# esp8266-dev.net
KiCad netlist of a schematic drawn in EAGLE
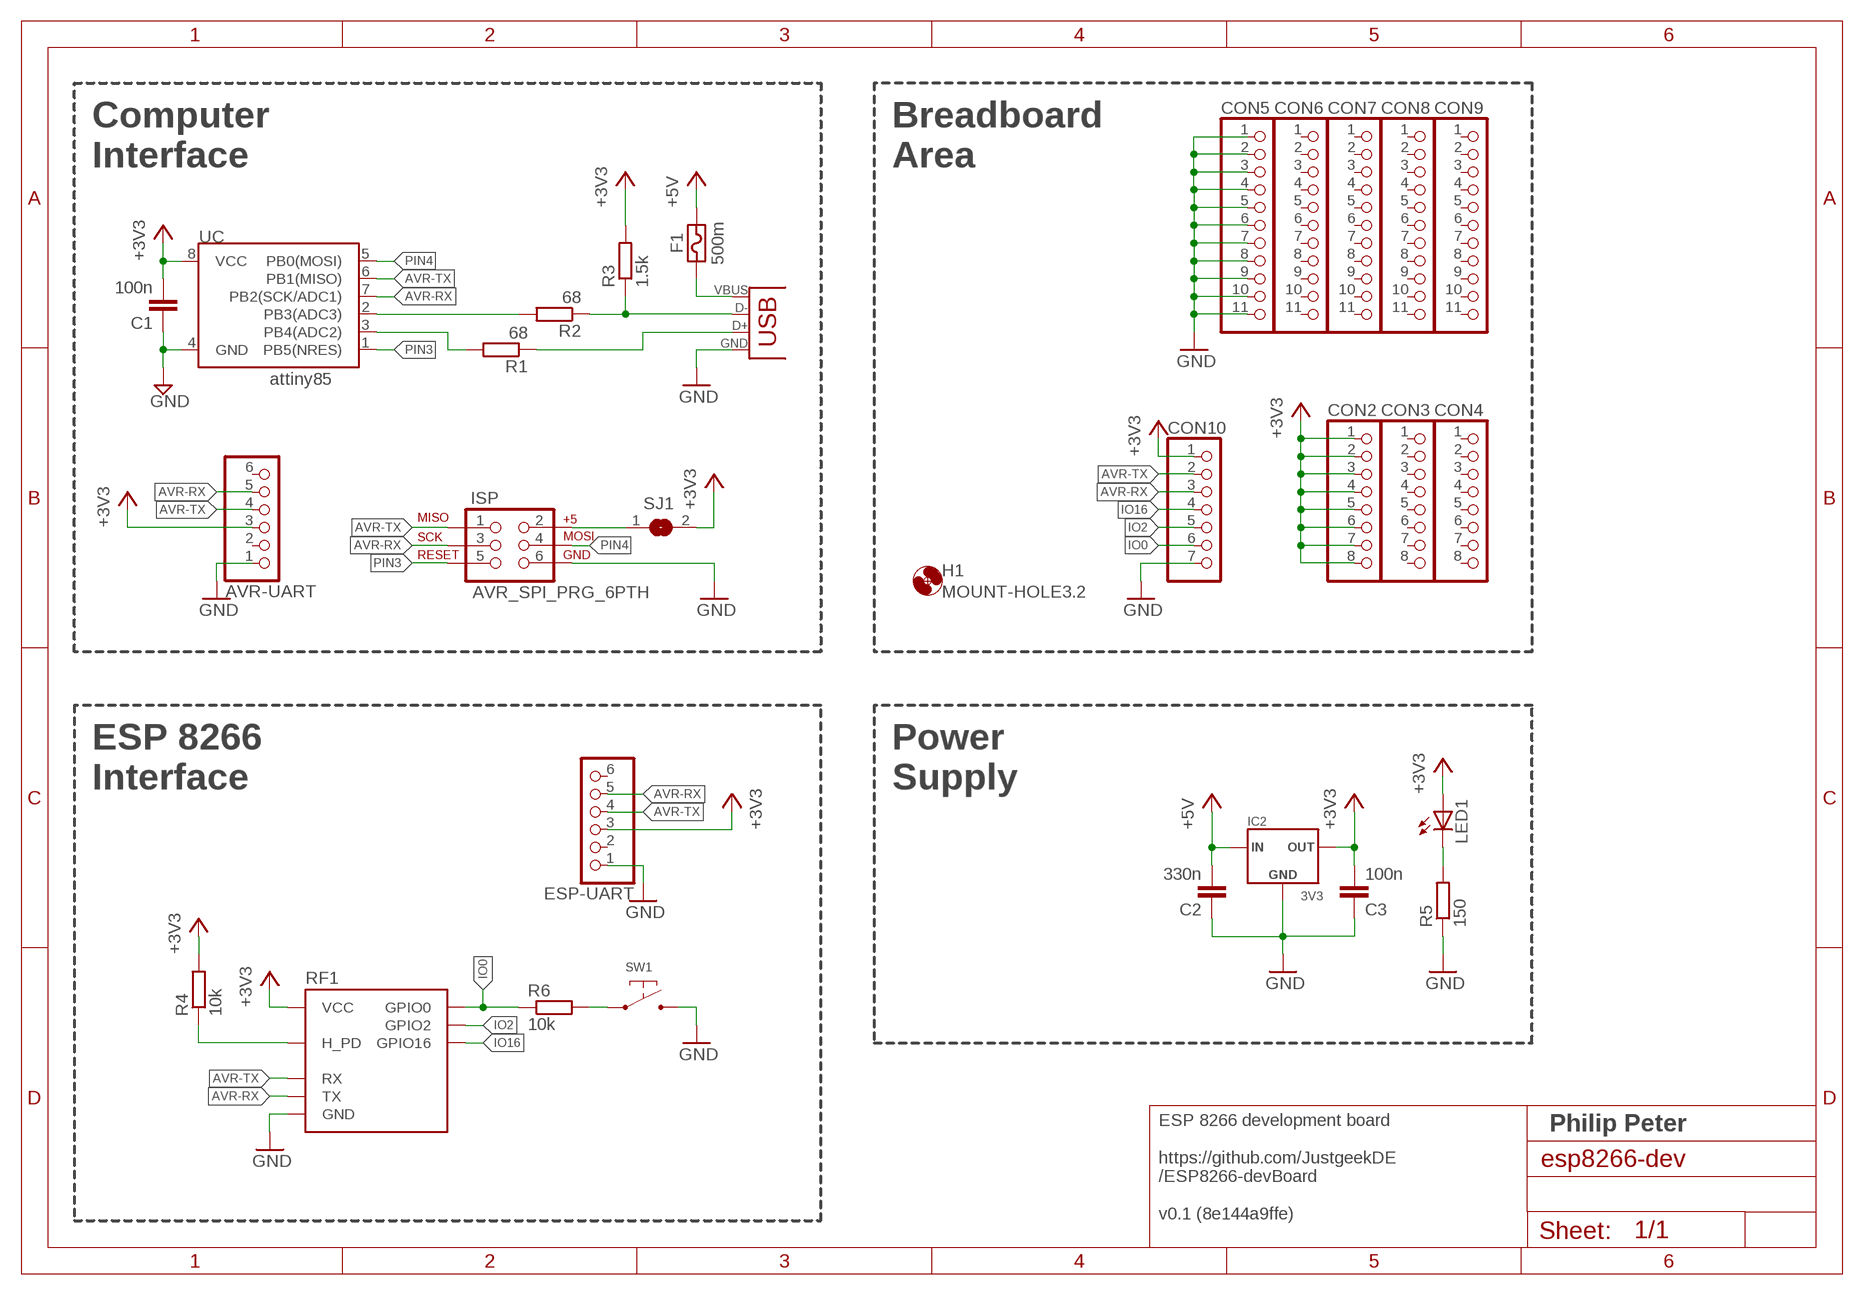
[diagram p0: schematic, sheet 1]

(export (version "E")
  (design (tool "Eeschema 10.0.6"))
  (components
    (comp (ref "AVR-UART")
      (value "GENERIC-1X6STANDARD")
      (footprint "eagle-import:PINHEADER-100MIL-1X6")
      (libsource (lib "eagle-import") (part "GENERIC-1X6STANDARD"))
    )
    (comp (ref "C1")
      (value "100n")
      (footprint "eagle-import:C025-025X050")
      (libsource (lib "eagle-import") (part "C-EU025-025X050"))
    )
    (comp (ref "C2")
      (value "330n")
      (footprint "eagle-import:C025-025X050")
      (libsource (lib "eagle-import") (part "C-EU025-025X050"))
    )
    (comp (ref "C3")
      (value "100n")
      (footprint "eagle-import:C025-025X050")
      (libsource (lib "eagle-import") (part "C-EU025-025X050"))
    )
    (comp (ref "CON1")
      (value "USBB-SOCKET")
      (footprint "eagle-import:PN61729-S")
      (libsource (lib "eagle-import") (part "USBB-SOCKET"))
    )
    (comp (ref "CON2")
      (value "GENERIC-1X8NOSILK")
      (footprint "eagle-import:PINHEADER-100MIL-1X8-NOSILK")
      (libsource (lib "eagle-import") (part "GENERIC-1X8NOSILK"))
    )
    (comp (ref "CON3")
      (value "GENERIC-1X8NOSILK")
      (footprint "eagle-import:PINHEADER-100MIL-1X8-NOSILK")
      (libsource (lib "eagle-import") (part "GENERIC-1X8NOSILK"))
    )
    (comp (ref "CON4")
      (value "GENERIC-1X8NOSILK")
      (footprint "eagle-import:PINHEADER-100MIL-1X8-NOSILK")
      (libsource (lib "eagle-import") (part "GENERIC-1X8NOSILK"))
    )
    (comp (ref "CON5")
      (value "GENERIC-1X11NOSILK")
      (footprint "eagle-import:PINHEADER-100MIL-1X11-NOSILK")
      (libsource (lib "eagle-import") (part "GENERIC-1X11NOSILK"))
    )
    (comp (ref "CON6")
      (value "GENERIC-1X11NOSILK")
      (footprint "eagle-import:PINHEADER-100MIL-1X11-NOSILK")
      (libsource (lib "eagle-import") (part "GENERIC-1X11NOSILK"))
    )
    (comp (ref "CON7")
      (value "GENERIC-1X11NOSILK")
      (footprint "eagle-import:PINHEADER-100MIL-1X11-NOSILK")
      (libsource (lib "eagle-import") (part "GENERIC-1X11NOSILK"))
    )
    (comp (ref "CON8")
      (value "GENERIC-1X11NOSILK")
      (footprint "eagle-import:PINHEADER-100MIL-1X11-NOSILK")
      (libsource (lib "eagle-import") (part "GENERIC-1X11NOSILK"))
    )
    (comp (ref "CON9")
      (value "GENERIC-1X11NOSILK")
      (footprint "eagle-import:PINHEADER-100MIL-1X11-NOSILK")
      (libsource (lib "eagle-import") (part "GENERIC-1X11NOSILK"))
    )
    (comp (ref "CON10")
      (value "GENERIC-1X7NOSILK")
      (footprint "eagle-import:PINHEADER-100MIL-1X7-NOSILK")
      (libsource (lib "eagle-import") (part "GENERIC-1X7NOSILK"))
    )
    (comp (ref "ESP-UART")
      (value "GENERIC-1X6STANDARD")
      (footprint "eagle-import:PINHEADER-100MIL-1X6")
      (libsource (lib "eagle-import") (part "GENERIC-1X6STANDARD"))
    )
    (comp (ref "F1")
      (value "500m")
      (footprint "eagle-import:FUSE-THT-100-MIL")
      (libsource (lib "eagle-import") (part "FUSETHT-5.1"))
    )
    (comp (ref "H1")
      (value "MOUNT-HOLE3.2")
      (footprint "eagle-import:3,2")
      (libsource (lib "eagle-import") (part "MOUNT-HOLE3.2"))
    )
    (comp (ref "IC2")
      (value "3V3")
      (footprint "eagle-import:TO220V")
      (libsource (lib "eagle-import") (part "REGULATOR-UA78M33TO220"))
    )
    (comp (ref "ISP")
      (value "AVR_SPI_PRG_6PTH")
      (footprint "eagle-import:2X3")
      (libsource (lib "eagle-import") (part "AVR_SPI_PRG_6PTH"))
    )
    (comp (ref "LED1")
      (value "LED3MM")
      (footprint "eagle-import:LED3MM")
      (libsource (lib "eagle-import") (part "LED3MM"))
    )
    (comp (ref "R1")
      (value "68")
      (footprint "eagle-import:0204_7")
      (libsource (lib "eagle-import") (part "R-EU_0204/7"))
    )
    (comp (ref "R2")
      (value "68")
      (footprint "eagle-import:0204_7")
      (libsource (lib "eagle-import") (part "R-EU_0204/7"))
    )
    (comp (ref "R3")
      (value "1.5k")
      (footprint "eagle-import:0204_7")
      (libsource (lib "eagle-import") (part "R-EU_0204/7"))
    )
    (comp (ref "R4")
      (value "10k")
      (footprint "eagle-import:0204_7")
      (libsource (lib "eagle-import") (part "R-EU_0204/7"))
    )
    (comp (ref "R5")
      (value "150")
      (footprint "eagle-import:0204_7")
      (libsource (lib "eagle-import") (part "R-EU_0204/7"))
    )
    (comp (ref "R6")
      (value "10k")
      (footprint "eagle-import:0204_7")
      (libsource (lib "eagle-import") (part "R-EU_0204/7"))
    )
    (comp (ref "RF1")
      (value "ESP2866-ESP-01THT-NOSILK")
      (footprint "eagle-import:ESP8266-ESP-01-NOSILK")
      (libsource (lib "eagle-import") (part "ESP2866-ESP-01THT-NOSILK"))
    )
    (comp (ref "SJ1") (value "SJ") (footprint "eagle-import:SJ") (libsource (lib "eagle-import") (part "SJ")))
    (comp (ref "SW1")
      (value "SWITCH-DEFAULT_OFF-DEFAULT")
      (footprint "eagle-import:SWITCH-GENERIC-4_PIN")
      (libsource (lib "eagle-import") (part "SWITCH-DEFAULT_OFF-DEFAULT"))
    )
    (comp (ref "UC")
      (value "ATTINY85")
      (footprint "eagle-import:DIP08")
      (libsource (lib "eagle-import") (part "ATTINY45DIP8"))
    )
  )
  (nets
    (net (code "1") (name "+3V3") (class "Default")
      (node (ref "AVR-UART") (pin "3") (pinfunction "3_3") (pintype "passive"))
      (node (ref "C1") (pin "2") (pinfunction "2_2") (pintype "passive"))
      (node (ref "C3") (pin "2") (pinfunction "2_2") (pintype "passive"))
      (node (ref "CON10") (pin "1") (pinfunction "1_1") (pintype "passive"))
      (node (ref "CON2") (pin "1") (pinfunction "1_1") (pintype "passive"))
      (node (ref "CON2") (pin "2") (pinfunction "2_2") (pintype "passive"))
      (node (ref "CON2") (pin "3") (pinfunction "3_3") (pintype "passive"))
      (node (ref "CON2") (pin "4") (pinfunction "4_4") (pintype "passive"))
      (node (ref "CON2") (pin "5") (pinfunction "5_5") (pintype "passive"))
      (node (ref "CON2") (pin "6") (pinfunction "6_6") (pintype "passive"))
      (node (ref "CON2") (pin "7") (pinfunction "7_7") (pintype "passive"))
      (node (ref "CON2") (pin "8") (pinfunction "8_8") (pintype "passive"))
      (node (ref "ESP-UART") (pin "3") (pinfunction "3_3") (pintype "passive"))
      (node (ref "IC2") (pin "3") (pinfunction "OUT_3") (pintype "bidirectional"))
      (node (ref "LED1") (pin "A") (pinfunction "A_A") (pintype "passive"))
      (node (ref "R3") (pin "2") (pinfunction "2_2") (pintype "passive"))
      (node (ref "R4") (pin "2") (pinfunction "2_2") (pintype "passive"))
      (node (ref "RF1") (pin "VCC") (pinfunction "VCC_VCC") (pintype "bidirectional"))
      (node (ref "SJ1") (pin "2") (pinfunction "2_2") (pintype "passive"))
      (node (ref "UC") (pin "8") (pinfunction "VCC_8") (pintype "bidirectional"))
    )
    (net (code "2") (name "+5V") (class "Default")
      (node (ref "C2") (pin "2") (pinfunction "2_2") (pintype "passive"))
      (node (ref "F1") (pin "P$2") (pinfunction "P$2_P$2") (pintype "bidirectional"))
      (node (ref "IC2") (pin "1") (pinfunction "IN_1") (pintype "bidirectional"))
    )
    (net (code "3") (name "AVR-RX") (class "Default")
      (node (ref "AVR-UART") (pin "5") (pinfunction "5_5") (pintype "passive"))
      (node (ref "CON10") (pin "3") (pinfunction "3_3") (pintype "passive"))
      (node (ref "ESP-UART") (pin "5") (pinfunction "5_5") (pintype "passive"))
      (node (ref "ISP") (pin "3") (pinfunction "3_3") (pintype "passive"))
      (node (ref "RF1") (pin "TX") (pinfunction "TX_TX") (pintype "bidirectional"))
      (node (ref "UC") (pin "7") (pinfunction "PB2(SCK/ADC1)_7") (pintype "bidirectional"))
    )
    (net (code "4") (name "AVR-TX") (class "Default")
      (node (ref "AVR-UART") (pin "4") (pinfunction "4_4") (pintype "passive"))
      (node (ref "CON10") (pin "2") (pinfunction "2_2") (pintype "passive"))
      (node (ref "ESP-UART") (pin "4") (pinfunction "4_4") (pintype "passive"))
      (node (ref "ISP") (pin "1") (pinfunction "1_1") (pintype "passive"))
      (node (ref "RF1") (pin "RX") (pinfunction "RX_RX") (pintype "bidirectional"))
      (node (ref "UC") (pin "6") (pinfunction "PB1(MISO)_6") (pintype "bidirectional"))
    )
    (net (code "5") (name "GND") (class "Default")
      (node (ref "AVR-UART") (pin "1") (pinfunction "1_1") (pintype "passive"))
      (node (ref "C1") (pin "1") (pinfunction "1_1") (pintype "passive"))
      (node (ref "C2") (pin "1") (pinfunction "1_1") (pintype "passive"))
      (node (ref "C3") (pin "1") (pinfunction "1_1") (pintype "passive"))
      (node (ref "CON1") (pin "4") (pinfunction "GND_4") (pintype "bidirectional"))
      (node (ref "CON10") (pin "7") (pinfunction "7_7") (pintype "passive"))
      (node (ref "CON5") (pin "1") (pinfunction "1_1") (pintype "passive"))
      (node (ref "CON5") (pin "10") (pinfunction "10_10") (pintype "passive"))
      (node (ref "CON5") (pin "11") (pinfunction "11_11") (pintype "passive"))
      (node (ref "CON5") (pin "2") (pinfunction "2_2") (pintype "passive"))
      (node (ref "CON5") (pin "3") (pinfunction "3_3") (pintype "passive"))
      (node (ref "CON5") (pin "4") (pinfunction "4_4") (pintype "passive"))
      (node (ref "CON5") (pin "5") (pinfunction "5_5") (pintype "passive"))
      (node (ref "CON5") (pin "6") (pinfunction "6_6") (pintype "passive"))
      (node (ref "CON5") (pin "7") (pinfunction "7_7") (pintype "passive"))
      (node (ref "CON5") (pin "8") (pinfunction "8_8") (pintype "passive"))
      (node (ref "CON5") (pin "9") (pinfunction "9_9") (pintype "passive"))
      (node (ref "ESP-UART") (pin "1") (pinfunction "1_1") (pintype "passive"))
      (node (ref "IC2") (pin "2") (pinfunction "GND_2") (pintype "bidirectional"))
      (node (ref "ISP") (pin "6") (pinfunction "6_6") (pintype "passive"))
      (node (ref "R5") (pin "1") (pinfunction "1_1") (pintype "passive"))
      (node (ref "RF1") (pin "GND") (pinfunction "GND_GND") (pintype "bidirectional"))
      (node (ref "SW1") (pin "P$3") (pinfunction "P$2_P$3") (pintype "bidirectional"))
      (node (ref "SW1") (pin "P$4") (pinfunction "P$2_P$4") (pintype "bidirectional"))
      (node (ref "UC") (pin "4") (pinfunction "GND_4") (pintype "bidirectional"))
    )
    (net (code "6") (name "IO0") (class "Default")
      (node (ref "CON10") (pin "6") (pinfunction "6_6") (pintype "passive"))
      (node (ref "R6") (pin "1") (pinfunction "1_1") (pintype "passive"))
      (node (ref "RF1") (pin "GPIO0") (pinfunction "GPIO0_GPIO0") (pintype "bidirectional"))
    )
    (net (code "7") (name "IO2") (class "Default")
      (node (ref "CON10") (pin "5") (pinfunction "5_5") (pintype "passive"))
      (node (ref "RF1") (pin "GPIO2") (pinfunction "GPIO2_GPIO2") (pintype "bidirectional"))
    )
    (net (code "8") (name "IO16") (class "Default")
      (node (ref "CON10") (pin "4") (pinfunction "4_4") (pintype "passive"))
      (node (ref "RF1") (pin "GPIO16") (pinfunction "GPIO16_GPIO16") (pintype "bidirectional"))
    )
    (net (code "9") (name "Net-(CON1-D+)") (class "Default")
      (node (ref "CON1") (pin "3") (pinfunction "D+_3") (pintype "bidirectional"))
      (node (ref "R1") (pin "1") (pinfunction "1_1") (pintype "passive"))
    )
    (net (code "10") (name "Net-(CON1-D-)") (class "Default")
      (node (ref "CON1") (pin "2") (pinfunction "D-_2") (pintype "bidirectional"))
      (node (ref "R2") (pin "1") (pinfunction "1_1") (pintype "passive"))
      (node (ref "R3") (pin "1") (pinfunction "1_1") (pintype "passive"))
    )
    (net (code "11") (name "Net-(CON1-VBUS)") (class "Default")
      (node (ref "CON1") (pin "1") (pinfunction "VBUS_1") (pintype "bidirectional"))
      (node (ref "F1") (pin "P$1") (pinfunction "P$1_P$1") (pintype "bidirectional"))
    )
    (net (code "12") (name "Net-(ISP-Pad2)") (class "Default")
      (node (ref "ISP") (pin "2") (pinfunction "2_2") (pintype "passive"))
      (node (ref "SJ1") (pin "1") (pinfunction "1_1") (pintype "passive"))
    )
    (net (code "13") (name "Net-(LED1-C)") (class "Default")
      (node (ref "LED1") (pin "K") (pinfunction "C_K") (pintype "passive"))
      (node (ref "R5") (pin "2") (pinfunction "2_2") (pintype "passive"))
    )
    (net (code "14") (name "Net-(R4-Pad1)") (class "Default")
      (node (ref "R4") (pin "1") (pinfunction "1_1") (pintype "passive"))
      (node (ref "RF1") (pin "H_PD") (pinfunction "H_PD_H_PD") (pintype "bidirectional"))
    )
    (net (code "15") (name "Net-(R6-Pad2)") (class "Default")
      (node (ref "R6") (pin "2") (pinfunction "2_2") (pintype "passive"))
      (node (ref "SW1") (pin "P$1") (pinfunction "P$1_P$1") (pintype "bidirectional"))
      (node (ref "SW1") (pin "P$2") (pinfunction "P$1_P$2") (pintype "bidirectional"))
    )
    (net (code "16") (name "Net-(UC-PB3(ADC3))") (class "Default")
      (node (ref "R2") (pin "2") (pinfunction "2_2") (pintype "passive"))
      (node (ref "UC") (pin "2") (pinfunction "PB3(ADC3)_2") (pintype "bidirectional"))
    )
    (net (code "17") (name "Net-(UC-PB4(ADC2))") (class "Default")
      (node (ref "R1") (pin "2") (pinfunction "2_2") (pintype "passive"))
      (node (ref "UC") (pin "3") (pinfunction "PB4(ADC2)_3") (pintype "bidirectional"))
    )
    (net (code "18") (name "PIN3") (class "Default")
      (node (ref "ISP") (pin "5") (pinfunction "5_5") (pintype "passive"))
      (node (ref "UC") (pin "1") (pinfunction "PB5(NRES)_1") (pintype "bidirectional"))
    )
    (net (code "19") (name "PIN4") (class "Default")
      (node (ref "ISP") (pin "4") (pinfunction "4_4") (pintype "passive"))
      (node (ref "UC") (pin "5") (pinfunction "PB0(MOSI)_5") (pintype "bidirectional"))
    )
    (net (code "20") (name "unconnected-(AVR-UART-Pad2)") (class "Default")
      (node (ref "AVR-UART") (pin "2") (pinfunction "2_2") (pintype "passive"))
    )
    (net (code "21") (name "unconnected-(AVR-UART-Pad6)") (class "Default")
      (node (ref "AVR-UART") (pin "6") (pinfunction "6_6") (pintype "passive"))
    )
    (net (code "22") (name "unconnected-(CON3-Pad1)") (class "Default")
      (node (ref "CON3") (pin "1") (pinfunction "1_1") (pintype "passive"))
    )
    (net (code "23") (name "unconnected-(CON3-Pad2)") (class "Default")
      (node (ref "CON3") (pin "2") (pinfunction "2_2") (pintype "passive"))
    )
    (net (code "24") (name "unconnected-(CON3-Pad3)") (class "Default")
      (node (ref "CON3") (pin "3") (pinfunction "3_3") (pintype "passive"))
    )
    (net (code "25") (name "unconnected-(CON3-Pad4)") (class "Default")
      (node (ref "CON3") (pin "4") (pinfunction "4_4") (pintype "passive"))
    )
    (net (code "26") (name "unconnected-(CON3-Pad5)") (class "Default")
      (node (ref "CON3") (pin "5") (pinfunction "5_5") (pintype "passive"))
    )
    (net (code "27") (name "unconnected-(CON3-Pad6)") (class "Default")
      (node (ref "CON3") (pin "6") (pinfunction "6_6") (pintype "passive"))
    )
    (net (code "28") (name "unconnected-(CON3-Pad7)") (class "Default")
      (node (ref "CON3") (pin "7") (pinfunction "7_7") (pintype "passive"))
    )
    (net (code "29") (name "unconnected-(CON3-Pad8)") (class "Default")
      (node (ref "CON3") (pin "8") (pinfunction "8_8") (pintype "passive"))
    )
    (net (code "30") (name "unconnected-(CON4-Pad1)") (class "Default")
      (node (ref "CON4") (pin "1") (pinfunction "1_1") (pintype "passive"))
    )
    (net (code "31") (name "unconnected-(CON4-Pad2)") (class "Default")
      (node (ref "CON4") (pin "2") (pinfunction "2_2") (pintype "passive"))
    )
    (net (code "32") (name "unconnected-(CON4-Pad3)") (class "Default")
      (node (ref "CON4") (pin "3") (pinfunction "3_3") (pintype "passive"))
    )
    (net (code "33") (name "unconnected-(CON4-Pad4)") (class "Default")
      (node (ref "CON4") (pin "4") (pinfunction "4_4") (pintype "passive"))
    )
    (net (code "34") (name "unconnected-(CON4-Pad5)") (class "Default")
      (node (ref "CON4") (pin "5") (pinfunction "5_5") (pintype "passive"))
    )
    (net (code "35") (name "unconnected-(CON4-Pad6)") (class "Default")
      (node (ref "CON4") (pin "6") (pinfunction "6_6") (pintype "passive"))
    )
    (net (code "36") (name "unconnected-(CON4-Pad7)") (class "Default")
      (node (ref "CON4") (pin "7") (pinfunction "7_7") (pintype "passive"))
    )
    (net (code "37") (name "unconnected-(CON4-Pad8)") (class "Default")
      (node (ref "CON4") (pin "8") (pinfunction "8_8") (pintype "passive"))
    )
    (net (code "38") (name "unconnected-(CON6-Pad1)") (class "Default")
      (node (ref "CON6") (pin "1") (pinfunction "1_1") (pintype "passive"))
    )
    (net (code "39") (name "unconnected-(CON6-Pad2)") (class "Default")
      (node (ref "CON6") (pin "2") (pinfunction "2_2") (pintype "passive"))
    )
    (net (code "40") (name "unconnected-(CON6-Pad3)") (class "Default")
      (node (ref "CON6") (pin "3") (pinfunction "3_3") (pintype "passive"))
    )
    (net (code "41") (name "unconnected-(CON6-Pad4)") (class "Default")
      (node (ref "CON6") (pin "4") (pinfunction "4_4") (pintype "passive"))
    )
    (net (code "42") (name "unconnected-(CON6-Pad5)") (class "Default")
      (node (ref "CON6") (pin "5") (pinfunction "5_5") (pintype "passive"))
    )
    (net (code "43") (name "unconnected-(CON6-Pad6)") (class "Default")
      (node (ref "CON6") (pin "6") (pinfunction "6_6") (pintype "passive"))
    )
    (net (code "44") (name "unconnected-(CON6-Pad7)") (class "Default")
      (node (ref "CON6") (pin "7") (pinfunction "7_7") (pintype "passive"))
    )
    (net (code "45") (name "unconnected-(CON6-Pad8)") (class "Default")
      (node (ref "CON6") (pin "8") (pinfunction "8_8") (pintype "passive"))
    )
    (net (code "46") (name "unconnected-(CON6-Pad9)") (class "Default")
      (node (ref "CON6") (pin "9") (pinfunction "9_9") (pintype "passive"))
    )
    (net (code "47") (name "unconnected-(CON6-Pad10)") (class "Default")
      (node (ref "CON6") (pin "10") (pinfunction "10_10") (pintype "passive"))
    )
    (net (code "48") (name "unconnected-(CON6-Pad11)") (class "Default")
      (node (ref "CON6") (pin "11") (pinfunction "11_11") (pintype "passive"))
    )
    (net (code "49") (name "unconnected-(CON7-Pad1)") (class "Default")
      (node (ref "CON7") (pin "1") (pinfunction "1_1") (pintype "passive"))
    )
    (net (code "50") (name "unconnected-(CON7-Pad2)") (class "Default")
      (node (ref "CON7") (pin "2") (pinfunction "2_2") (pintype "passive"))
    )
    (net (code "51") (name "unconnected-(CON7-Pad3)") (class "Default")
      (node (ref "CON7") (pin "3") (pinfunction "3_3") (pintype "passive"))
    )
    (net (code "52") (name "unconnected-(CON7-Pad4)") (class "Default")
      (node (ref "CON7") (pin "4") (pinfunction "4_4") (pintype "passive"))
    )
    (net (code "53") (name "unconnected-(CON7-Pad5)") (class "Default")
      (node (ref "CON7") (pin "5") (pinfunction "5_5") (pintype "passive"))
    )
    (net (code "54") (name "unconnected-(CON7-Pad6)") (class "Default")
      (node (ref "CON7") (pin "6") (pinfunction "6_6") (pintype "passive"))
    )
    (net (code "55") (name "unconnected-(CON7-Pad7)") (class "Default")
      (node (ref "CON7") (pin "7") (pinfunction "7_7") (pintype "passive"))
    )
    (net (code "56") (name "unconnected-(CON7-Pad8)") (class "Default")
      (node (ref "CON7") (pin "8") (pinfunction "8_8") (pintype "passive"))
    )
    (net (code "57") (name "unconnected-(CON7-Pad9)") (class "Default")
      (node (ref "CON7") (pin "9") (pinfunction "9_9") (pintype "passive"))
    )
    (net (code "58") (name "unconnected-(CON7-Pad10)") (class "Default")
      (node (ref "CON7") (pin "10") (pinfunction "10_10") (pintype "passive"))
    )
    (net (code "59") (name "unconnected-(CON7-Pad11)") (class "Default")
      (node (ref "CON7") (pin "11") (pinfunction "11_11") (pintype "passive"))
    )
    (net (code "60") (name "unconnected-(CON8-Pad1)") (class "Default")
      (node (ref "CON8") (pin "1") (pinfunction "1_1") (pintype "passive"))
    )
    (net (code "61") (name "unconnected-(CON8-Pad2)") (class "Default")
      (node (ref "CON8") (pin "2") (pinfunction "2_2") (pintype "passive"))
    )
    (net (code "62") (name "unconnected-(CON8-Pad3)") (class "Default")
      (node (ref "CON8") (pin "3") (pinfunction "3_3") (pintype "passive"))
    )
    (net (code "63") (name "unconnected-(CON8-Pad4)") (class "Default")
      (node (ref "CON8") (pin "4") (pinfunction "4_4") (pintype "passive"))
    )
    (net (code "64") (name "unconnected-(CON8-Pad5)") (class "Default")
      (node (ref "CON8") (pin "5") (pinfunction "5_5") (pintype "passive"))
    )
    (net (code "65") (name "unconnected-(CON8-Pad6)") (class "Default")
      (node (ref "CON8") (pin "6") (pinfunction "6_6") (pintype "passive"))
    )
    (net (code "66") (name "unconnected-(CON8-Pad7)") (class "Default")
      (node (ref "CON8") (pin "7") (pinfunction "7_7") (pintype "passive"))
    )
    (net (code "67") (name "unconnected-(CON8-Pad8)") (class "Default")
      (node (ref "CON8") (pin "8") (pinfunction "8_8") (pintype "passive"))
    )
    (net (code "68") (name "unconnected-(CON8-Pad9)") (class "Default")
      (node (ref "CON8") (pin "9") (pinfunction "9_9") (pintype "passive"))
    )
    (net (code "69") (name "unconnected-(CON8-Pad10)") (class "Default")
      (node (ref "CON8") (pin "10") (pinfunction "10_10") (pintype "passive"))
    )
    (net (code "70") (name "unconnected-(CON8-Pad11)") (class "Default")
      (node (ref "CON8") (pin "11") (pinfunction "11_11") (pintype "passive"))
    )
    (net (code "71") (name "unconnected-(CON9-Pad1)") (class "Default")
      (node (ref "CON9") (pin "1") (pinfunction "1_1") (pintype "passive"))
    )
    (net (code "72") (name "unconnected-(CON9-Pad2)") (class "Default")
      (node (ref "CON9") (pin "2") (pinfunction "2_2") (pintype "passive"))
    )
    (net (code "73") (name "unconnected-(CON9-Pad3)") (class "Default")
      (node (ref "CON9") (pin "3") (pinfunction "3_3") (pintype "passive"))
    )
    (net (code "74") (name "unconnected-(CON9-Pad4)") (class "Default")
      (node (ref "CON9") (pin "4") (pinfunction "4_4") (pintype "passive"))
    )
    (net (code "75") (name "unconnected-(CON9-Pad5)") (class "Default")
      (node (ref "CON9") (pin "5") (pinfunction "5_5") (pintype "passive"))
    )
    (net (code "76") (name "unconnected-(CON9-Pad6)") (class "Default")
      (node (ref "CON9") (pin "6") (pinfunction "6_6") (pintype "passive"))
    )
    (net (code "77") (name "unconnected-(CON9-Pad7)") (class "Default")
      (node (ref "CON9") (pin "7") (pinfunction "7_7") (pintype "passive"))
    )
    (net (code "78") (name "unconnected-(CON9-Pad8)") (class "Default")
      (node (ref "CON9") (pin "8") (pinfunction "8_8") (pintype "passive"))
    )
    (net (code "79") (name "unconnected-(CON9-Pad9)") (class "Default")
      (node (ref "CON9") (pin "9") (pinfunction "9_9") (pintype "passive"))
    )
    (net (code "80") (name "unconnected-(CON9-Pad10)") (class "Default")
      (node (ref "CON9") (pin "10") (pinfunction "10_10") (pintype "passive"))
    )
    (net (code "81") (name "unconnected-(CON9-Pad11)") (class "Default")
      (node (ref "CON9") (pin "11") (pinfunction "11_11") (pintype "passive"))
    )
    (net (code "82") (name "unconnected-(ESP-UART-Pad2)") (class "Default")
      (node (ref "ESP-UART") (pin "2") (pinfunction "2_2") (pintype "passive"))
    )
    (net (code "83") (name "unconnected-(ESP-UART-Pad6)") (class "Default")
      (node (ref "ESP-UART") (pin "6") (pinfunction "6_6") (pintype "passive"))
    )
  )
)
